# SmartHiveClient_220V_V2_0.net
KiCad netlist of a schematic drawn in Altium Designer
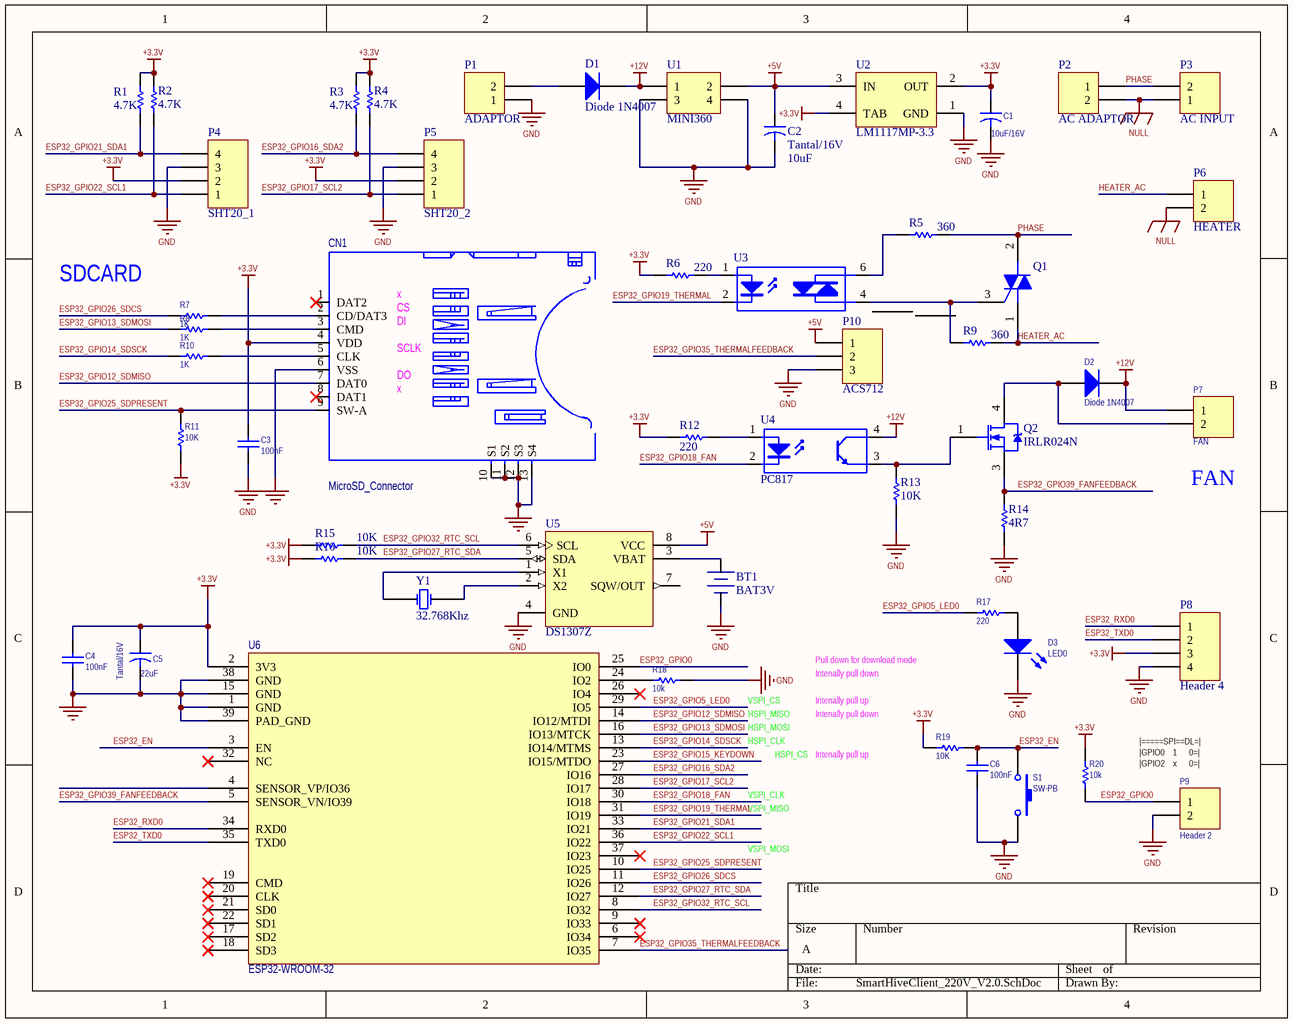
[diagram p0: SmartHiveClient_220V_V2.0.SchDoc]

(export (version "E")
  (design (tool "Eeschema 10.0.6"))
  (components
    (comp (ref "BT1")
      (value "BAT3V")
      (footprint "BTH2032_DIP")
      (description "Battry Backup")
      (fields (field (name "DESIGNER") "Abbas Basereh"))
      (libsource (lib "Mofidi3D") (part "Battry Backup"))
    )
    (comp (ref "C1")
      (value "10uF/16V")
      (footprint "Cap electrolitic radial 5x11-2")
      (description "Capacitor")
      (fields (field (name "PUBLISHER") "Altium Limited"))
      (libsource (lib "Miscellaneous Devices") (part "Cap2"))
    )
    (comp (ref "C2")
      (value "Tantal/16V")
      (footprint "Cap electrolitic radial 5x11-2")
      (description "Capacitor")
      (fields (field (name "ALTIUM_VALUE") "10uF") (field (name "PUBLISHER") "Altium Limited"))
      (libsource (lib "Miscellaneous Devices") (part "Cap2"))
    )
    (comp (ref "C3")
      (value "100nF")
      (footprint "CAP0805")
      (description "Capacitor")
      (fields (field (name "PUBLISHER") "Altium Limited"))
      (libsource (lib "Miscellaneous Devices") (part "Cap"))
    )
    (comp (ref "C4")
      (value "100nF")
      (footprint "CAP0805")
      (description "Capacitor")
      (fields (field (name "PUBLISHER") "Altium Limited"))
      (libsource (lib "Miscellaneous Devices") (part "Cap"))
    )
    (comp (ref "C5")
      (value "Tantal/16V")
      (footprint "CAP_TANTAL_TYPE_B")
      (description "Capacitor")
      (fields (field (name "ALTIUM_VALUE") "22uF") (field (name "PUBLISHER") "Altium Limited"))
      (libsource (lib "Miscellaneous Devices") (part "Cap2"))
    )
    (comp (ref "C6")
      (value "100nF")
      (footprint "CAP0805")
      (description "Capacitor")
      (fields (field (name "PUBLISHER") "Altium Limited"))
      (libsource (lib "Miscellaneous Devices") (part "Cap"))
    )
    (comp (ref "CN1")
      (value "MicroSD_Connector")
      (footprint "MICRO_SD_TFP-09-2-12B")
      (libsource (lib "Mofidi3D") (part "MicroSD_Connector"))
    )
    (comp (ref "D1")
      (value "Diode 1N4007")
      (footprint "DO-241AC")
      (description "1 Amp General Purpose Rectifier")
      (fields (field (name "PUBLISHER") "Altium Limited"))
      (libsource (lib "Miscellaneous Devices") (part "Diode 1N4007"))
    )
    (comp (ref "D2")
      (value "Diode 1N4007")
      (footprint "DO-241AC")
      (description "1 Amp General Purpose Rectifier")
      (fields (field (name "PUBLISHER") "Altium Limited"))
      (libsource (lib "Miscellaneous Devices") (part "Diode 1N4007"))
    )
    (comp (ref "D3")
      (value "LED0")
      (footprint "LED_0805")
      (description "Typical INFRARED GaAs LED")
      (fields (field (name "PUBLISHER") "Altium Limited"))
      (libsource (lib "Miscellaneous Devices") (part "LED0"))
    )
    (comp (ref "P1")
      (value "ADAPTOR")
      (footprint "KF301 2PIN")
      (description "Header, 2-Pin")
      (fields (field (name "PUBLISHER") "Altium Limited"))
      (libsource (lib "") (part "Header 2_3"))
    )
    (comp (ref "P2")
      (value "AC ADAPTOR")
      (footprint "KF301 2PIN")
      (description "Header, 2-Pin")
      (fields (field (name "PUBLISHER") "Altium Limited"))
      (libsource (lib "") (part "Header 2_1"))
    )
    (comp (ref "P3")
      (value "AC INPUT")
      (footprint "MSTB 2,5/2-G-5,08")
      (description "Header, 2-Pin")
      (fields (field (name "PUBLISHER") "Altium Limited"))
      (libsource (lib "") (part "Header 2_2"))
    )
    (comp (ref "P4")
      (value "SHT20_1")
      (footprint "XH-4PIN-RA")
      (description "Header, 4-Pin")
      (fields (field (name "PUBLISHER") "Altium Limited"))
      (libsource (lib "") (part "Header 4_1"))
    )
    (comp (ref "P5")
      (value "SHT20_2")
      (footprint "XH-4PIN-RA")
      (description "Header, 4-Pin")
      (fields (field (name "PUBLISHER") "Altium Limited"))
      (libsource (lib "") (part "Header 4_1"))
    )
    (comp (ref "P6")
      (value "HEATER")
      (footprint "MSTB 2,5/2-G-5,08")
      (description "Header, 2-Pin")
      (fields (field (name "PUBLISHER") "Altium Limited"))
      (libsource (lib "Miscellaneous Connectors") (part "Header 2"))
    )
    (comp (ref "P7")
      (value "FAN")
      (footprint "MSTB 2,5/2-G-5,08")
      (description "Header, 2-Pin")
      (fields (field (name "PUBLISHER") "Altium Limited"))
      (libsource (lib "Miscellaneous Connectors") (part "Header 2"))
    )
    (comp (ref "P8")
      (value "Header 4")
      (footprint "HDR1X4")
      (description "Header, 4-Pin")
      (fields (field (name "PUBLISHER") "Altium Limited"))
      (libsource (lib "Miscellaneous Connectors") (part "Header 4"))
    )
    (comp (ref "P9")
      (value "Header 2")
      (footprint "Jumper Small - 2.54 - Black")
      (description "Header, 2-Pin")
      (fields (field (name "PUBLISHER") "Altium Limited"))
      (libsource (lib "Miscellaneous Connectors") (part "Header 2"))
    )
    (comp (ref "P10")
      (value "ACS712")
      (footprint "HDR1X3")
      (description "ACS712 CURRENT")
      (fields (field (name "PUBLISHER") "Altium Limited"))
      (libsource (lib "Miscellaneous Connectors") (part "Header 3"))
    )
    (comp (ref "Q1")
      (value "BT139")
      (footprint "TO-220 AB WITH HEAT SINK")
      (description "Silicon Bidirectional Triode Thyristor")
      (fields (field (name "PUBLISHER") "Altium Limited"))
      (libsource (lib "Miscellaneous Devices") (part "Triac"))
    )
    (comp (ref "Q2")
      (value "IRLR024N")
      (footprint "TO252-3M")
      (description "HEXFET Power MOSFET")
      (fields (field (name "PUBLISHER") "Altium Limited"))
      (libsource (lib "IR Discrete MOSFET - Power") (part "IRLR024N"))
    )
    (comp (ref "R1")
      (value "4.7K")
      (footprint "RES0805")
      (description "Resistor")
      (fields (field (name "PUBLISHER") "Altium Limited"))
      (libsource (lib "Miscellaneous Devices") (part "Res1"))
    )
    (comp (ref "R2")
      (value "4.7K")
      (footprint "RES0805")
      (description "Resistor")
      (fields (field (name "PUBLISHER") "Altium Limited"))
      (libsource (lib "Miscellaneous Devices") (part "Res1"))
    )
    (comp (ref "R3")
      (value "4.7K")
      (footprint "RES0805")
      (description "Resistor")
      (fields (field (name "PUBLISHER") "Altium Limited"))
      (libsource (lib "Miscellaneous Devices") (part "Res1"))
    )
    (comp (ref "R4")
      (value "4.7K")
      (footprint "RES0805")
      (description "Resistor")
      (fields (field (name "PUBLISHER") "Altium Limited"))
      (libsource (lib "Miscellaneous Devices") (part "Res1"))
    )
    (comp (ref "R5")
      (value "360")
      (footprint "RES1206")
      (description "Resistor")
      (fields (field (name "PUBLISHER") "Altium Limited"))
      (libsource (lib "Miscellaneous Devices") (part "Res1"))
    )
    (comp (ref "R6")
      (value "220")
      (footprint "RES0805")
      (description "Resistor")
      (fields (field (name "PUBLISHER") "Altium Limited"))
      (libsource (lib "Miscellaneous Devices") (part "Res1"))
    )
    (comp (ref "R7")
      (value "1K")
      (footprint "RES0805")
      (description "Resistor")
      (fields (field (name "PUBLISHER") "Altium Limited"))
      (libsource (lib "Miscellaneous Devices") (part "Res1"))
    )
    (comp (ref "R8")
      (value "1K")
      (footprint "RES0805")
      (description "Resistor")
      (fields (field (name "PUBLISHER") "Altium Limited"))
      (libsource (lib "Miscellaneous Devices") (part "Res1"))
    )
    (comp (ref "R9")
      (value "360")
      (footprint "RES1206")
      (description "Resistor")
      (fields (field (name "PUBLISHER") "Altium Limited"))
      (libsource (lib "Miscellaneous Devices") (part "Res1"))
    )
    (comp (ref "R10")
      (value "1K")
      (footprint "RES0805")
      (description "Resistor")
      (fields (field (name "PUBLISHER") "Altium Limited"))
      (libsource (lib "Miscellaneous Devices") (part "Res1"))
    )
    (comp (ref "R11")
      (value "10K")
      (footprint "RES0805")
      (description "Resistor")
      (fields (field (name "PUBLISHER") "Altium Limited"))
      (libsource (lib "Miscellaneous Devices") (part "Res1"))
    )
    (comp (ref "R12")
      (value "220")
      (footprint "RES0805")
      (description "Resistor")
      (fields (field (name "PUBLISHER") "Altium Limited"))
      (libsource (lib "Miscellaneous Devices") (part "Res1"))
    )
    (comp (ref "R13")
      (value "10K")
      (footprint "RES0805")
      (description "Resistor")
      (fields (field (name "PUBLISHER") "Altium Limited"))
      (libsource (lib "Miscellaneous Devices") (part "Res1"))
    )
    (comp (ref "R14")
      (value "4R7")
      (footprint "RES2512")
      (description "Size:2512,1%")
      (fields (field (name "PUBLISHER") "Altium Limited"))
      (libsource (lib "Miscellaneous Devices") (part "Res1"))
    )
    (comp (ref "R15")
      (value "10K")
      (footprint "RES0805")
      (description "Resistor")
      (fields (field (name "PUBLISHER") "Altium Limited"))
      (libsource (lib "Miscellaneous Devices") (part "Res1"))
    )
    (comp (ref "R16")
      (value "10K")
      (footprint "RES0805")
      (description "Resistor")
      (fields (field (name "PUBLISHER") "Altium Limited"))
      (libsource (lib "Miscellaneous Devices") (part "Res1"))
    )
    (comp (ref "R17")
      (value "220")
      (footprint "RES0805")
      (description "Resistor")
      (fields (field (name "PUBLISHER") "Altium Limited"))
      (libsource (lib "Miscellaneous Devices") (part "Res1"))
    )
    (comp (ref "R18")
      (value "10k")
      (footprint "RES0805")
      (description "Resistor")
      (fields (field (name "PUBLISHER") "Altium Limited"))
      (libsource (lib "Miscellaneous Devices") (part "Res1"))
    )
    (comp (ref "R19")
      (value "10K")
      (footprint "RES0805")
      (description "Resistor")
      (fields (field (name "PUBLISHER") "Altium Limited"))
      (libsource (lib "Miscellaneous Devices") (part "Res1"))
    )
    (comp (ref "R20")
      (value "10k")
      (footprint "RES0805")
      (description "Resistor")
      (fields (field (name "PUBLISHER") "Altium Limited"))
      (libsource (lib "Miscellaneous Devices") (part "Res1"))
    )
    (comp (ref "S1")
      (value "SW-PB")
      (footprint "SW-2PIN-SMD")
      (description "Switch")
      (fields (field (name "PUBLISHER") "Altium Limited"))
      (libsource (lib "Miscellaneous Devices") (part "SW-PB"))
    )
    (comp (ref "U1")
      (value "MINI360")
      (footprint "MINI360-DCDC")
      (fields (field (name "PUBLISHER") "Altium Limited"))
      (libsource (lib "Miscellaneous Connectors") (part "Header 2X2"))
    )
    (comp (ref "U2")
      (value "LM1117MP-3.3")
      (footprint "SOT223_4")
      (description "800mA Low-Dropout Linear Regulator, 4-pin SOT-223")
      (fields
        (field (name "MANUFACTURER") "National Semiconductor")
        (field (name "PUBLISHER") "Altium Limited")
      )
      (libsource (lib "NSC LDO") (part "LM1117MP-3.3"))
    )
    (comp (ref "U3")
      (value "MOC3063")
      (footprint "DIP-6")
      (description "Opto-Triac")
      (fields (field (name "PUBLISHER") "Altium Limited"))
      (libsource (lib "Miscellaneous Devices") (part "Opto TRIAC"))
    )
    (comp (ref "U4")
      (value "PC817")
      (footprint "DIP_4")
      (description "4-Pin Phototransistor Optocoupler")
      (fields (field (name "PUBLISHER") "Altium Limited"))
      (libsource (lib "Miscellaneous Devices") (part "Optoisolator1"))
    )
    (comp (ref "U5")
      (value "DS1307Z")
      (footprint "SO-8N")
      (description "64 X 8 Serial Real-Time Clock")
      (fields (field (name "PUBLISHER") "Altium Limited"))
      (libsource (lib "Dallas Peripheral Real Time Clock") (part "DS1307Z"))
    )
    (comp (ref "U6")
      (value "ESP32-WROOM-32")
      (footprint "ESP32-WROOM-32D")
      (description "ESP32  a single chip 2.4 GHz Wi-Fi and Bluetooth combo chip")
      (libsource (lib "Mofidi3D") (part "ESP32-WROOM-32"))
    )
    (comp (ref "Y1")
      (value "32.768Khz")
      (footprint "Crystal_NC308")
      (description "XTAL Crystal")
      (fields (field (name "DESIGNER") "ABBAS BASEREH"))
      (libsource (lib "Mofidi3D") (part "XTAL_Crystal"))
    )
  )
  (nets
    (net (code "1") (name "+3.3V") (class "Default")
      (node (ref "C1") (pin "1") (pinfunction "1_1") (pintype "passive"))
      (node (ref "C3") (pin "2") (pinfunction "2_2") (pintype "passive"))
      (node (ref "C4") (pin "2") (pinfunction "2_2") (pintype "passive"))
      (node (ref "C5") (pin "1") (pinfunction "1_1") (pintype "passive"))
      (node (ref "CN1") (pin "4") (pinfunction "VDD_4") (pintype "passive"))
      (node (ref "P4") (pin "2") (pinfunction "2_2") (pintype "passive"))
      (node (ref "P5") (pin "2") (pinfunction "2_2") (pintype "passive"))
      (node (ref "P8") (pin "3") (pinfunction "3_3") (pintype "passive"))
      (node (ref "R1") (pin "2") (pinfunction "2_2") (pintype "passive"))
      (node (ref "R11") (pin "2") (pinfunction "2_2") (pintype "passive"))
      (node (ref "R12") (pin "1") (pinfunction "1_1") (pintype "passive"))
      (node (ref "R15") (pin "2") (pinfunction "2_2") (pintype "passive"))
      (node (ref "R16") (pin "2") (pinfunction "2_2") (pintype "passive"))
      (node (ref "R19") (pin "2") (pinfunction "2_2") (pintype "passive"))
      (node (ref "R2") (pin "2") (pinfunction "2_2") (pintype "passive"))
      (node (ref "R20") (pin "2") (pinfunction "2_2") (pintype "passive"))
      (node (ref "R3") (pin "2") (pinfunction "2_2") (pintype "passive"))
      (node (ref "R4") (pin "2") (pinfunction "2_2") (pintype "passive"))
      (node (ref "R6") (pin "2") (pinfunction "2_2") (pintype "passive"))
      (node (ref "U2") (pin "2") (pinfunction "OUT_2") (pintype "power_in"))
      (node (ref "U2") (pin "4") (pinfunction "TAB_4") (pintype "power_in"))
      (node (ref "U6") (pin "2") (pinfunction "3V3_2") (pintype "power_in"))
    )
    (net (code "2") (name "+5V") (class "Default")
      (node (ref "C2") (pin "1") (pinfunction "1_1") (pintype "passive"))
      (node (ref "P10") (pin "1") (pinfunction "1_1") (pintype "passive"))
      (node (ref "U1") (pin "2") (pinfunction "2_2") (pintype "passive"))
      (node (ref "U2") (pin "3") (pinfunction "IN_3") (pintype "power_in"))
      (node (ref "U5") (pin "8") (pinfunction "VCC_8") (pintype "power_in"))
    )
    (net (code "3") (name "+12V") (class "Default")
      (node (ref "D1") (pin "2") (pinfunction "K_2") (pintype "passive"))
      (node (ref "D2") (pin "2") (pinfunction "K_2") (pintype "passive"))
      (node (ref "P7") (pin "1") (pinfunction "1_1") (pintype "passive"))
      (node (ref "U1") (pin "1") (pinfunction "1_1") (pintype "passive"))
      (node (ref "U4") (pin "4") (pinfunction "C_4") (pintype "passive"))
    )
    (net (code "4") (name "/ESP32_EN") (class "Default")
      (node (ref "C6") (pin "2") (pinfunction "2_2") (pintype "passive"))
      (node (ref "R19") (pin "1") (pinfunction "1_1") (pintype "passive"))
      (node (ref "S1") (pin "1") (pinfunction "1_1") (pintype "passive"))
      (node (ref "U6") (pin "3") (pinfunction "EN_3") (pintype "passive"))
    )
    (net (code "5") (name "/ESP32_GPIO0") (class "Default")
      (node (ref "P9") (pin "1") (pinfunction "1_1") (pintype "passive"))
      (node (ref "R20") (pin "1") (pinfunction "1_1") (pintype "passive"))
      (node (ref "U6") (pin "25") (pinfunction "IO0_25") (pintype "passive"))
    )
    (net (code "6") (name "/ESP32_GPIO5_LED0") (class "Default")
      (node (ref "R17") (pin "1") (pinfunction "1_1") (pintype "passive"))
      (node (ref "U6") (pin "29") (pinfunction "IO5_29") (pintype "passive"))
    )
    (net (code "7") (name "/ESP32_GPIO12_SDMISO") (class "Default")
      (node (ref "CN1") (pin "7") (pinfunction "DAT0_7") (pintype "passive"))
      (node (ref "U6") (pin "14") (pinfunction "IO12/MTDI_14") (pintype "passive"))
    )
    (net (code "8") (name "/ESP32_GPIO13_SDMOSI") (class "Default")
      (node (ref "R8") (pin "2") (pinfunction "2_2") (pintype "passive"))
      (node (ref "U6") (pin "16") (pinfunction "IO13/MTCK_16") (pintype "passive"))
    )
    (net (code "9") (name "/ESP32_GPIO14_SDSCK") (class "Default")
      (node (ref "R10") (pin "2") (pinfunction "2_2") (pintype "passive"))
      (node (ref "U6") (pin "13") (pinfunction "IO14/MTMS_13") (pintype "passive"))
    )
    (net (code "10") (name "/ESP32_GPIO15_KEYDOWN") (class "Default")
      (node (ref "U6") (pin "23") (pinfunction "IO15/MTDO_23") (pintype "passive"))
    )
    (net (code "11") (name "/ESP32_GPIO16_SDA2") (class "Default")
      (node (ref "P5") (pin "4") (pinfunction "4_4") (pintype "passive"))
      (node (ref "R3") (pin "1") (pinfunction "1_1") (pintype "passive"))
      (node (ref "U6") (pin "27") (pinfunction "IO16_27") (pintype "passive"))
    )
    (net (code "12") (name "/ESP32_GPIO17_SCL2") (class "Default")
      (node (ref "P5") (pin "1") (pinfunction "1_1") (pintype "passive"))
      (node (ref "R4") (pin "1") (pinfunction "1_1") (pintype "passive"))
      (node (ref "U6") (pin "28") (pinfunction "IO17_28") (pintype "passive"))
    )
    (net (code "13") (name "/ESP32_GPIO18_FAN") (class "Default")
      (node (ref "U4") (pin "2") (pinfunction "K_2") (pintype "passive"))
      (node (ref "U6") (pin "30") (pinfunction "IO18_30") (pintype "passive"))
    )
    (net (code "14") (name "/ESP32_GPIO19_THERMAL") (class "Default")
      (node (ref "U3") (pin "2") (pinfunction "K_2") (pintype "passive"))
      (node (ref "U6") (pin "31") (pinfunction "IO19_31") (pintype "passive"))
    )
    (net (code "15") (name "/ESP32_GPIO21_SDA1") (class "Default")
      (node (ref "P4") (pin "4") (pinfunction "4_4") (pintype "passive"))
      (node (ref "R1") (pin "1") (pinfunction "1_1") (pintype "passive"))
      (node (ref "U6") (pin "33") (pinfunction "IO21_33") (pintype "passive"))
    )
    (net (code "16") (name "/ESP32_GPIO22_SCL1") (class "Default")
      (node (ref "P4") (pin "1") (pinfunction "1_1") (pintype "passive"))
      (node (ref "R2") (pin "1") (pinfunction "1_1") (pintype "passive"))
      (node (ref "U6") (pin "36") (pinfunction "IO22_36") (pintype "passive"))
    )
    (net (code "17") (name "/ESP32_GPIO25_SDPRESENT") (class "Default")
      (node (ref "CN1") (pin "9") (pinfunction "SW-A_9") (pintype "passive"))
      (node (ref "R11") (pin "1") (pinfunction "1_1") (pintype "passive"))
      (node (ref "U6") (pin "10") (pinfunction "IO25_10") (pintype "passive"))
    )
    (net (code "18") (name "/ESP32_GPIO26_SDCS") (class "Default")
      (node (ref "R7") (pin "2") (pinfunction "2_2") (pintype "passive"))
      (node (ref "U6") (pin "11") (pinfunction "IO26_11") (pintype "passive"))
    )
    (net (code "19") (name "/ESP32_GPIO27_RTC_SDA") (class "Default")
      (node (ref "R16") (pin "1") (pinfunction "1_1") (pintype "passive"))
      (node (ref "U5") (pin "5") (pinfunction "SDA_5") (pintype "bidirectional"))
      (node (ref "U6") (pin "12") (pinfunction "IO27_12") (pintype "passive"))
    )
    (net (code "20") (name "/ESP32_GPIO32_RTC_SCL") (class "Default")
      (node (ref "R15") (pin "1") (pinfunction "1_1") (pintype "passive"))
      (node (ref "U5") (pin "6") (pinfunction "SCL_6") (pintype "input"))
      (node (ref "U6") (pin "8") (pinfunction "IO32_8") (pintype "passive"))
    )
    (net (code "21") (name "/ESP32_GPIO35_THERMALFEEDBACK") (class "Default")
      (node (ref "P10") (pin "2") (pinfunction "2_2") (pintype "passive"))
      (node (ref "U6") (pin "7") (pinfunction "IO35_7") (pintype "passive"))
    )
    (net (code "22") (name "/ESP32_GPIO39_FANFEEDBACK") (class "Default")
      (node (ref "Q2") (pin "3") (pinfunction "S_3") (pintype "passive"))
      (node (ref "R14") (pin "2") (pinfunction "2_2") (pintype "passive"))
      (node (ref "U6") (pin "5") (pinfunction "SENSOR_VN/IO39_5") (pintype "passive"))
    )
    (net (code "23") (name "/ESP32_RXD0") (class "Default")
      (node (ref "P8") (pin "1") (pinfunction "1_1") (pintype "passive"))
      (node (ref "U6") (pin "34") (pinfunction "RXD0_34") (pintype "passive"))
    )
    (net (code "24") (name "/ESP32_TXD0") (class "Default")
      (node (ref "P8") (pin "2") (pinfunction "2_2") (pintype "passive"))
      (node (ref "U6") (pin "35") (pinfunction "TXD0_35") (pintype "passive"))
    )
    (net (code "25") (name "/HEATER_AC") (class "Default")
      (node (ref "P6") (pin "1") (pinfunction "1_1") (pintype "passive"))
      (node (ref "Q1") (pin "1") (pinfunction "M1_1") (pintype "passive"))
      (node (ref "R9") (pin "1") (pinfunction "1_1") (pintype "passive"))
    )
    (net (code "26") (name "/PHASE") (class "Default")
      (node (ref "P2") (pin "1") (pinfunction "1_1") (pintype "passive"))
      (node (ref "P3") (pin "2") (pinfunction "2_2") (pintype "passive"))
      (node (ref "Q1") (pin "2") (pinfunction "M2_2") (pintype "passive"))
      (node (ref "R5") (pin "1") (pinfunction "1_1") (pintype "passive"))
    )
    (net (code "27") (name "GND") (class "Default")
      (node (ref "BT1") (pin "2") (pinfunction "-_2") (pintype "passive"))
      (node (ref "C1") (pin "2") (pinfunction "2_2") (pintype "passive"))
      (node (ref "C2") (pin "2") (pinfunction "2_2") (pintype "passive"))
      (node (ref "C3") (pin "1") (pinfunction "1_1") (pintype "passive"))
      (node (ref "C4") (pin "1") (pinfunction "1_1") (pintype "passive"))
      (node (ref "C5") (pin "2") (pinfunction "2_2") (pintype "passive"))
      (node (ref "C6") (pin "1") (pinfunction "1_1") (pintype "passive"))
      (node (ref "CN1") (pin "10") (pinfunction "S1_10") (pintype "passive"))
      (node (ref "CN1") (pin "11") (pinfunction "S2_11") (pintype "passive"))
      (node (ref "CN1") (pin "12") (pinfunction "S3_12") (pintype "passive"))
      (node (ref "CN1") (pin "13") (pinfunction "S4_13") (pintype "passive"))
      (node (ref "CN1") (pin "6") (pinfunction "VSS_6") (pintype "passive"))
      (node (ref "D3") (pin "2") (pinfunction "K_2") (pintype "passive"))
      (node (ref "P1") (pin "1") (pinfunction "1_1") (pintype "passive"))
      (node (ref "P10") (pin "3") (pinfunction "3_3") (pintype "passive"))
      (node (ref "P4") (pin "3") (pinfunction "3_3") (pintype "passive"))
      (node (ref "P5") (pin "3") (pinfunction "3_3") (pintype "passive"))
      (node (ref "P8") (pin "4") (pinfunction "4_4") (pintype "passive"))
      (node (ref "P9") (pin "2") (pinfunction "2_2") (pintype "passive"))
      (node (ref "R13") (pin "1") (pinfunction "1_1") (pintype "passive"))
      (node (ref "R14") (pin "1") (pinfunction "1_1") (pintype "passive"))
      (node (ref "R18") (pin "1") (pinfunction "1_1") (pintype "passive"))
      (node (ref "S1") (pin "2") (pinfunction "2_2") (pintype "passive"))
      (node (ref "U1") (pin "3") (pinfunction "3_3") (pintype "passive"))
      (node (ref "U1") (pin "4") (pinfunction "4_4") (pintype "passive"))
      (node (ref "U2") (pin "1") (pinfunction "GND_1") (pintype "power_in"))
      (node (ref "U5") (pin "4") (pinfunction "GND_4") (pintype "power_in"))
      (node (ref "U6") (pin "1") (pinfunction "GND_1") (pintype "power_in"))
      (node (ref "U6") (pin "15") (pinfunction "GND_15") (pintype "power_in"))
      (node (ref "U6") (pin "38") (pinfunction "GND_38") (pintype "power_in"))
      (node (ref "U6") (pin "39") (pinfunction "PAD_GND_39") (pintype "passive"))
    )
    (net (code "28") (name "NULL") (class "Default")
      (node (ref "P2") (pin "2") (pinfunction "2_2") (pintype "passive"))
      (node (ref "P3") (pin "1") (pinfunction "1_1") (pintype "passive"))
      (node (ref "P6") (pin "2") (pinfunction "2_2") (pintype "passive"))
    )
    (net (code "29") (name "Net-(BT1-+)") (class "Default")
      (node (ref "BT1") (pin "1") (pinfunction "+_1") (pintype "passive"))
      (node (ref "U5") (pin "3") (pinfunction "VBAT_3") (pintype "power_in"))
    )
    (net (code "30") (name "Net-(CN1-CD{slash}DAT3)") (class "Default")
      (node (ref "CN1") (pin "2") (pinfunction "CD/DAT3_2") (pintype "passive"))
      (node (ref "R7") (pin "1") (pinfunction "1_1") (pintype "passive"))
    )
    (net (code "31") (name "Net-(CN1-CLK)") (class "Default")
      (node (ref "CN1") (pin "5") (pinfunction "CLK_5") (pintype "passive"))
      (node (ref "R10") (pin "1") (pinfunction "1_1") (pintype "passive"))
    )
    (net (code "32") (name "Net-(CN1-CMD)") (class "Default")
      (node (ref "CN1") (pin "3") (pinfunction "CMD_3") (pintype "passive"))
      (node (ref "R8") (pin "1") (pinfunction "1_1") (pintype "passive"))
    )
    (net (code "33") (name "Net-(D1-A)") (class "Default")
      (node (ref "D1") (pin "1") (pinfunction "A_1") (pintype "passive"))
      (node (ref "P1") (pin "2") (pinfunction "2_2") (pintype "passive"))
    )
    (net (code "34") (name "Net-(D2-A)") (class "Default")
      (node (ref "D2") (pin "1") (pinfunction "A_1") (pintype "passive"))
      (node (ref "P7") (pin "2") (pinfunction "2_2") (pintype "passive"))
      (node (ref "Q2") (pin "4") (pinfunction "D_4") (pintype "passive"))
    )
    (net (code "35") (name "Net-(D3-A)") (class "Default")
      (node (ref "D3") (pin "1") (pinfunction "A_1") (pintype "passive"))
      (node (ref "R17") (pin "2") (pinfunction "2_2") (pintype "passive"))
    )
    (net (code "36") (name "Net-(Q1-G)") (class "Default")
      (node (ref "Q1") (pin "3") (pinfunction "G_3") (pintype "passive"))
      (node (ref "R9") (pin "2") (pinfunction "2_2") (pintype "passive"))
      (node (ref "U3") (pin "4") (pinfunction "A/K_4") (pintype "passive"))
    )
    (net (code "37") (name "Net-(Q2-G)") (class "Default")
      (node (ref "Q2") (pin "1") (pinfunction "G_1") (pintype "passive"))
      (node (ref "R13") (pin "2") (pinfunction "2_2") (pintype "passive"))
      (node (ref "U4") (pin "3") (pinfunction "E_3") (pintype "passive"))
    )
    (net (code "38") (name "Net-(R5-Pad2)") (class "Default")
      (node (ref "R5") (pin "2") (pinfunction "2_2") (pintype "passive"))
      (node (ref "U3") (pin "6") (pinfunction "A/K_6") (pintype "passive"))
    )
    (net (code "39") (name "Net-(U3-A)") (class "Default")
      (node (ref "R6") (pin "1") (pinfunction "1_1") (pintype "passive"))
      (node (ref "U3") (pin "1") (pinfunction "A_1") (pintype "passive"))
    )
    (net (code "40") (name "Net-(U4-A)") (class "Default")
      (node (ref "R12") (pin "2") (pinfunction "2_2") (pintype "passive"))
      (node (ref "U4") (pin "1") (pinfunction "A_1") (pintype "passive"))
    )
    (net (code "41") (name "Net-(U5-X1)") (class "Default")
      (node (ref "U5") (pin "1") (pinfunction "X1_1") (pintype "input"))
      (node (ref "Y1") (pin "1") (pinfunction "OSC1_1") (pintype "passive"))
    )
    (net (code "42") (name "Net-(U5-X2)") (class "Default")
      (node (ref "U5") (pin "2") (pinfunction "X2_2") (pintype "input"))
      (node (ref "Y1") (pin "2") (pinfunction "OSC2_2") (pintype "passive"))
    )
    (net (code "43") (name "Net-(U6-IO2)") (class "Default")
      (node (ref "R18") (pin "2") (pinfunction "2_2") (pintype "passive"))
      (node (ref "U6") (pin "24") (pinfunction "IO2_24") (pintype "passive"))
    )
    (net (code "44") (name "unconnected-(CN1-DAT1-Pad8)") (class "Default")
      (node (ref "CN1") (pin "8") (pinfunction "DAT1_8") (pintype "passive+no_connect"))
    )
    (net (code "45") (name "unconnected-(CN1-DAT2-Pad1)") (class "Default")
      (node (ref "CN1") (pin "1") (pinfunction "DAT2_1") (pintype "passive+no_connect"))
    )
    (net (code "46") (name "unconnected-(U3-NC-Pad3)") (class "Default")
      (node (ref "U3") (pin "3") (pinfunction "NC_3") (pintype "passive"))
    )
    (net (code "47") (name "unconnected-(U3-NC-Pad5)") (class "Default")
      (node (ref "U3") (pin "5") (pinfunction "NC_5") (pintype "passive"))
    )
    (net (code "48") (name "unconnected-(U5-SQW{slash}OUT-Pad7)") (class "Default")
      (node (ref "U5") (pin "7") (pinfunction "SQW/OUT_7") (pintype "output"))
    )
    (net (code "49") (name "unconnected-(U6-CLK-Pad20)") (class "Default")
      (node (ref "U6") (pin "20") (pinfunction "CLK_20") (pintype "passive+no_connect"))
    )
    (net (code "50") (name "unconnected-(U6-CMD-Pad19)") (class "Default")
      (node (ref "U6") (pin "19") (pinfunction "CMD_19") (pintype "passive+no_connect"))
    )
    (net (code "51") (name "unconnected-(U6-IO4-Pad26)") (class "Default")
      (node (ref "U6") (pin "26") (pinfunction "IO4_26") (pintype "passive+no_connect"))
    )
    (net (code "52") (name "unconnected-(U6-IO23-Pad37)") (class "Default")
      (node (ref "U6") (pin "37") (pinfunction "IO23_37") (pintype "passive+no_connect"))
    )
    (net (code "53") (name "unconnected-(U6-IO33-Pad9)") (class "Default")
      (node (ref "U6") (pin "9") (pinfunction "IO33_9") (pintype "passive+no_connect"))
    )
    (net (code "54") (name "unconnected-(U6-IO34-Pad6)") (class "Default")
      (node (ref "U6") (pin "6") (pinfunction "IO34_6") (pintype "passive+no_connect"))
    )
    (net (code "55") (name "unconnected-(U6-NC-Pad32)") (class "Default")
      (node (ref "U6") (pin "32") (pinfunction "NC_32") (pintype "passive+no_connect"))
    )
    (net (code "56") (name "unconnected-(U6-SD0-Pad21)") (class "Default")
      (node (ref "U6") (pin "21") (pinfunction "SD0_21") (pintype "passive+no_connect"))
    )
    (net (code "57") (name "unconnected-(U6-SD1-Pad22)") (class "Default")
      (node (ref "U6") (pin "22") (pinfunction "SD1_22") (pintype "passive+no_connect"))
    )
    (net (code "58") (name "unconnected-(U6-SD2-Pad17)") (class "Default")
      (node (ref "U6") (pin "17") (pinfunction "SD2_17") (pintype "passive+no_connect"))
    )
    (net (code "59") (name "unconnected-(U6-SD3-Pad18)") (class "Default")
      (node (ref "U6") (pin "18") (pinfunction "SD3_18") (pintype "passive+no_connect"))
    )
    (net (code "60") (name "unconnected-(U6-SENSOR_VP{slash}IO36-Pad4)") (class "Default")
      (node (ref "U6") (pin "4") (pinfunction "SENSOR_VP/IO36_4") (pintype "passive"))
    )
  )
)
